# 595shiftOut.net
KiCad netlist of a schematic drawn in EAGLE
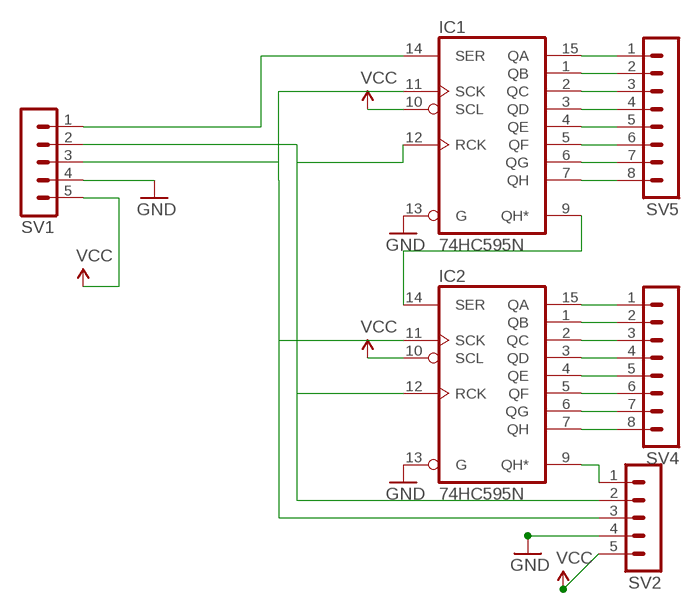
[diagram p0: schematic, sheet 1]

(export (version "E")
  (design (tool "Eeschema 10.0.6"))
  (components
    (comp (ref "IC1")
      (value "74HC595N")
      (footprint "eagle-import:DIL16")
      (libsource (lib "eagle-import") (part "74595NHC"))
    )
    (comp (ref "IC2")
      (value "74HC595N")
      (footprint "eagle-import:DIL16")
      (libsource (lib "eagle-import") (part "74595NHC"))
    )
    (comp (ref "SV1")
      (value "MA05-1")
      (footprint "eagle-import:MA05-1")
      (libsource (lib "eagle-import") (part "MA05-1"))
    )
    (comp (ref "SV2")
      (value "MA05-1")
      (footprint "eagle-import:MA05-1")
      (libsource (lib "eagle-import") (part "MA05-1"))
    )
    (comp (ref "SV4")
      (value "MA08-1")
      (footprint "eagle-import:MA08-1")
      (libsource (lib "eagle-import") (part "MA08-1"))
    )
    (comp (ref "SV5")
      (value "MA08-1")
      (footprint "eagle-import:MA08-1")
      (libsource (lib "eagle-import") (part "MA08-1"))
    )
  )
  (nets
    (net (code "1") (name "GND") (class "Default")
      (node (ref "IC1") (pin "13") (pinfunction "G_13") (pintype "input"))
      (node (ref "IC2") (pin "13") (pinfunction "G_13") (pintype "input"))
      (node (ref "SV1") (pin "4") (pinfunction "4_4") (pintype "passive"))
      (node (ref "SV2") (pin "4") (pinfunction "4_4") (pintype "passive"))
    )
    (net (code "2") (name "Net-(IC1A-QA)") (class "Default")
      (node (ref "IC1") (pin "15") (pinfunction "QA_15") (pintype "tri_state"))
      (node (ref "SV5") (pin "1") (pinfunction "1_1") (pintype "passive"))
    )
    (net (code "3") (name "Net-(IC1A-QB)") (class "Default")
      (node (ref "IC1") (pin "1") (pinfunction "QB_1") (pintype "tri_state"))
      (node (ref "SV5") (pin "2") (pinfunction "2_2") (pintype "passive"))
    )
    (net (code "4") (name "Net-(IC1A-QC)") (class "Default")
      (node (ref "IC1") (pin "2") (pinfunction "QC_2") (pintype "tri_state"))
      (node (ref "SV5") (pin "3") (pinfunction "3_3") (pintype "passive"))
    )
    (net (code "5") (name "Net-(IC1A-QD)") (class "Default")
      (node (ref "IC1") (pin "3") (pinfunction "QD_3") (pintype "tri_state"))
      (node (ref "SV5") (pin "4") (pinfunction "4_4") (pintype "passive"))
    )
    (net (code "6") (name "Net-(IC1A-QE)") (class "Default")
      (node (ref "IC1") (pin "4") (pinfunction "QE_4") (pintype "tri_state"))
      (node (ref "SV5") (pin "5") (pinfunction "5_5") (pintype "passive"))
    )
    (net (code "7") (name "Net-(IC1A-QF)") (class "Default")
      (node (ref "IC1") (pin "5") (pinfunction "QF_5") (pintype "tri_state"))
      (node (ref "SV5") (pin "6") (pinfunction "6_6") (pintype "passive"))
    )
    (net (code "8") (name "Net-(IC1A-QG)") (class "Default")
      (node (ref "IC1") (pin "6") (pinfunction "QG_6") (pintype "tri_state"))
      (node (ref "SV5") (pin "7") (pinfunction "7_7") (pintype "passive"))
    )
    (net (code "9") (name "Net-(IC1A-QH)") (class "Default")
      (node (ref "IC1") (pin "7") (pinfunction "QH_7") (pintype "tri_state"))
      (node (ref "SV5") (pin "8") (pinfunction "8_8") (pintype "passive"))
    )
    (net (code "10") (name "Net-(IC1A-QH*)") (class "Default")
      (node (ref "IC1") (pin "9") (pinfunction "QH*_9") (pintype "tri_state"))
      (node (ref "IC2") (pin "14") (pinfunction "SER_14") (pintype "input"))
    )
    (net (code "11") (name "Net-(IC1A-RCK)") (class "Default")
      (node (ref "IC1") (pin "12") (pinfunction "RCK_12") (pintype "input"))
      (node (ref "IC2") (pin "12") (pinfunction "RCK_12") (pintype "input"))
      (node (ref "SV1") (pin "2") (pinfunction "2_2") (pintype "passive"))
      (node (ref "SV2") (pin "2") (pinfunction "2_2") (pintype "passive"))
    )
    (net (code "12") (name "Net-(IC1A-SCK)") (class "Default")
      (node (ref "IC1") (pin "11") (pinfunction "SCK_11") (pintype "input"))
      (node (ref "IC2") (pin "11") (pinfunction "SCK_11") (pintype "input"))
      (node (ref "SV1") (pin "3") (pinfunction "3_3") (pintype "passive"))
      (node (ref "SV2") (pin "3") (pinfunction "3_3") (pintype "passive"))
    )
    (net (code "13") (name "Net-(IC1A-SER)") (class "Default")
      (node (ref "IC1") (pin "14") (pinfunction "SER_14") (pintype "input"))
      (node (ref "SV1") (pin "1") (pinfunction "1_1") (pintype "passive"))
    )
    (net (code "14") (name "Net-(IC2A-QA)") (class "Default")
      (node (ref "IC2") (pin "15") (pinfunction "QA_15") (pintype "tri_state"))
      (node (ref "SV4") (pin "1") (pinfunction "1_1") (pintype "passive"))
    )
    (net (code "15") (name "Net-(IC2A-QB)") (class "Default")
      (node (ref "IC2") (pin "1") (pinfunction "QB_1") (pintype "tri_state"))
      (node (ref "SV4") (pin "2") (pinfunction "2_2") (pintype "passive"))
    )
    (net (code "16") (name "Net-(IC2A-QC)") (class "Default")
      (node (ref "IC2") (pin "2") (pinfunction "QC_2") (pintype "tri_state"))
      (node (ref "SV4") (pin "3") (pinfunction "3_3") (pintype "passive"))
    )
    (net (code "17") (name "Net-(IC2A-QD)") (class "Default")
      (node (ref "IC2") (pin "3") (pinfunction "QD_3") (pintype "tri_state"))
      (node (ref "SV4") (pin "4") (pinfunction "4_4") (pintype "passive"))
    )
    (net (code "18") (name "Net-(IC2A-QE)") (class "Default")
      (node (ref "IC2") (pin "4") (pinfunction "QE_4") (pintype "tri_state"))
      (node (ref "SV4") (pin "5") (pinfunction "5_5") (pintype "passive"))
    )
    (net (code "19") (name "Net-(IC2A-QF)") (class "Default")
      (node (ref "IC2") (pin "5") (pinfunction "QF_5") (pintype "tri_state"))
      (node (ref "SV4") (pin "6") (pinfunction "6_6") (pintype "passive"))
    )
    (net (code "20") (name "Net-(IC2A-QG)") (class "Default")
      (node (ref "IC2") (pin "6") (pinfunction "QG_6") (pintype "tri_state"))
      (node (ref "SV4") (pin "7") (pinfunction "7_7") (pintype "passive"))
    )
    (net (code "21") (name "Net-(IC2A-QH)") (class "Default")
      (node (ref "IC2") (pin "7") (pinfunction "QH_7") (pintype "tri_state"))
      (node (ref "SV4") (pin "8") (pinfunction "8_8") (pintype "passive"))
    )
    (net (code "22") (name "Net-(IC2A-QH*)") (class "Default")
      (node (ref "IC2") (pin "9") (pinfunction "QH*_9") (pintype "tri_state"))
      (node (ref "SV2") (pin "1") (pinfunction "1_1") (pintype "passive"))
    )
    (net (code "23") (name "VCC") (class "Default")
      (node (ref "IC1") (pin "10") (pinfunction "SCL_10") (pintype "input"))
      (node (ref "IC2") (pin "10") (pinfunction "SCL_10") (pintype "input"))
      (node (ref "SV1") (pin "5") (pinfunction "5_5") (pintype "passive"))
      (node (ref "SV2") (pin "5") (pinfunction "5_5") (pintype "passive"))
    )
  )
)
